# LM317_Variable_Regulator.net
KiCad netlist of a schematic drawn in EAGLE
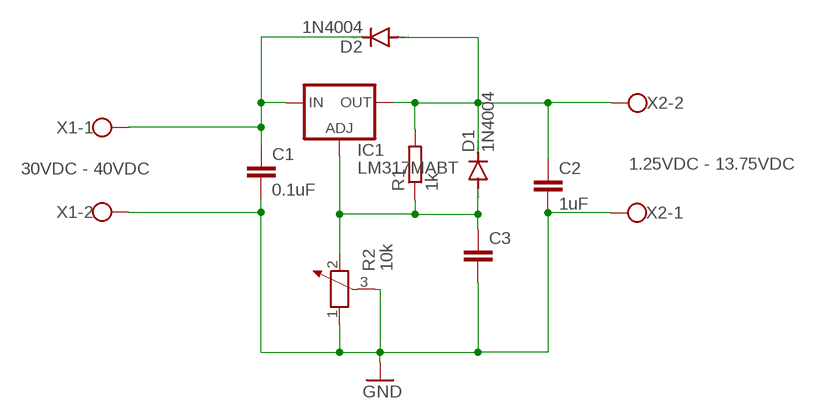
[diagram p0: schematic, sheet 1]

(export (version "E")
  (design (tool "Eeschema 10.0.6"))
  (components
    (comp (ref "C1")
      (value "0.1uF")
      (footprint "eagle-import:C025-024X044")
      (libsource (lib "eagle-import") (part "C-EU025-024X044"))
    )
    (comp (ref "C2")
      (value "1uF")
      (footprint "eagle-import:C025-024X044")
      (libsource (lib "eagle-import") (part "C-EU025-024X044"))
    )
    (comp (ref "C3")
      (value "C-EU025-024X044")
      (footprint "eagle-import:C025-024X044")
      (libsource (lib "eagle-import") (part "C-EU025-024X044"))
    )
    (comp (ref "D1")
      (value "1N4004")
      (footprint "eagle-import:DO41-10")
      (libsource (lib "eagle-import") (part "1N4004"))
    )
    (comp (ref "D2")
      (value "1N4004")
      (footprint "eagle-import:DO41-10")
      (libsource (lib "eagle-import") (part "1N4004"))
    )
    (comp (ref "IC1")
      (value "LM317MABT")
      (footprint "eagle-import:TO220L1")
      (libsource (lib "eagle-import") (part "LM317?MABT"))
    )
    (comp (ref "R1")
      (value "1k")
      (footprint "eagle-import:0204_7")
      (libsource (lib "eagle-import") (part "R-EU_0204/7"))
    )
    (comp (ref "R2")
      (value "10k")
      (footprint "eagle-import:PT-10")
      (libsource (lib "eagle-import") (part "POTENTIOMETER_PT-10"))
    )
    (comp (ref "X1")
      (value "30VDC - 40VDC")
      (footprint "eagle-import:W237-102")
      (fields (field (name "MPN") "237-102"))
      (libsource (lib "eagle-import") (part "W237-102"))
    )
    (comp (ref "X2")
      (value "1.25VDC - 13.75VDC")
      (footprint "eagle-import:W237-102")
      (fields (field (name "MPN") "237-102"))
      (libsource (lib "eagle-import") (part "W237-102"))
    )
  )
  (nets
    (net (code "1") (name "GND") (class "Default")
      (node (ref "C1") (pin "2") (pinfunction "2_2") (pintype "passive"))
      (node (ref "C2") (pin "2") (pinfunction "2_2") (pintype "passive"))
      (node (ref "C3") (pin "2") (pinfunction "2_2") (pintype "passive"))
      (node (ref "R2") (pin "1") (pinfunction "1_1") (pintype "passive"))
      (node (ref "R2") (pin "3") (pinfunction "3_3") (pintype "passive"))
      (node (ref "X1") (pin "2") (pinfunction "KL_2") (pintype "passive"))
      (node (ref "X2") (pin "1") (pinfunction "KL_1") (pintype "passive"))
    )
    (net (code "2") (name "Net-(IC1-ADJ)") (class "Default")
      (node (ref "C3") (pin "1") (pinfunction "1_1") (pintype "passive"))
      (node (ref "D1") (pin "A") (pinfunction "A_A") (pintype "passive"))
      (node (ref "IC1") (pin "1") (pinfunction "ADJ_1") (pintype "input"))
      (node (ref "R1") (pin "1") (pinfunction "1_1") (pintype "passive"))
      (node (ref "R2") (pin "2") (pinfunction "2_2") (pintype "passive"))
    )
    (net (code "3") (name "Net-(IC1-IN)") (class "Default")
      (node (ref "C1") (pin "1") (pinfunction "1_1") (pintype "passive"))
      (node (ref "D2") (pin "C") (pinfunction "C_C") (pintype "passive"))
      (node (ref "IC1") (pin "3") (pinfunction "IN_3") (pintype "input"))
      (node (ref "X1") (pin "1") (pinfunction "KL_1") (pintype "passive"))
    )
    (net (code "4") (name "Net-(IC1-OUT)") (class "Default")
      (node (ref "C2") (pin "1") (pinfunction "1_1") (pintype "passive"))
      (node (ref "D1") (pin "C") (pinfunction "C_C") (pintype "passive"))
      (node (ref "D2") (pin "A") (pinfunction "A_A") (pintype "passive"))
      (node (ref "IC1") (pin "2") (pinfunction "OUT_2") (pintype "passive"))
      (node (ref "R1") (pin "2") (pinfunction "2_2") (pintype "passive"))
      (node (ref "X2") (pin "2") (pinfunction "KL_2") (pintype "passive"))
    )
  )
)
